# PGTN021_octasource_controls.net
KiCad netlist of a schematic drawn in EAGLE
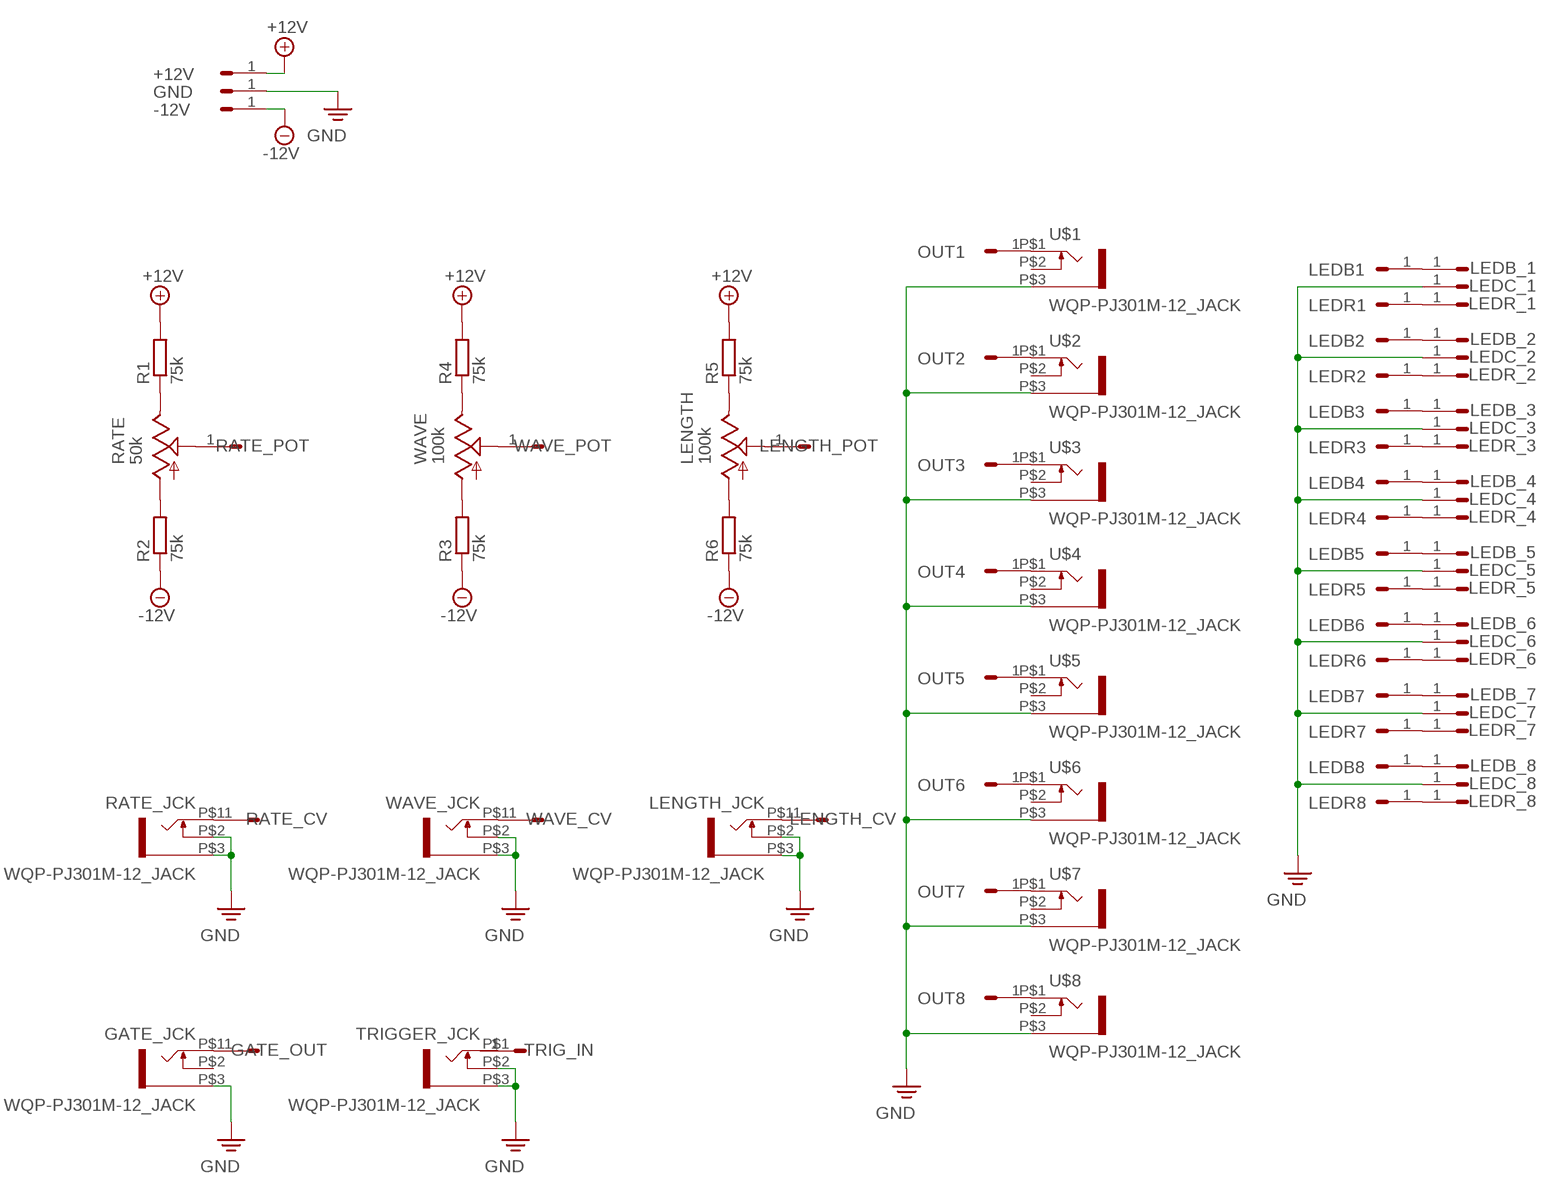
[diagram p0: schematic, sheet 1]

(export (version "E")
  (design (tool "Eeschema 10.0.6"))
  (components
    (comp (ref "+12V")
      (value "HEADER/MALE/01")
      (footprint "eagle-import:HEADER_MALE_01")
      (libsource (lib "eagle-import") (part "HEADER/MALE/01"))
    )
    (comp (ref "-12V")
      (value "HEADER/MALE/01")
      (footprint "eagle-import:HEADER_MALE_01")
      (libsource (lib "eagle-import") (part "HEADER/MALE/01"))
    )
    (comp (ref "GATE_JCK")
      (value "WQP-PJ301M-12_JACK")
      (footprint "eagle-import:WQP-PJ301M-12_JACK")
      (libsource (lib "eagle-import") (part "WQP-PJ301M-12_JACK"))
    )
    (comp (ref "GATE_OUT")
      (value "HEADER/MALE/01")
      (footprint "eagle-import:HEADER_MALE_01")
      (libsource (lib "eagle-import") (part "HEADER/MALE/01"))
    )
    (comp (ref "GND")
      (value "HEADER/MALE/01")
      (footprint "eagle-import:HEADER_MALE_01")
      (libsource (lib "eagle-import") (part "HEADER/MALE/01"))
    )
    (comp (ref "LEDB1")
      (value "HEADER/MALE/01")
      (footprint "eagle-import:HEADER_MALE_01")
      (libsource (lib "eagle-import") (part "HEADER/MALE/01"))
    )
    (comp (ref "LEDB2")
      (value "HEADER/MALE/01")
      (footprint "eagle-import:HEADER_MALE_01")
      (libsource (lib "eagle-import") (part "HEADER/MALE/01"))
    )
    (comp (ref "LEDB3")
      (value "HEADER/MALE/01")
      (footprint "eagle-import:HEADER_MALE_01")
      (libsource (lib "eagle-import") (part "HEADER/MALE/01"))
    )
    (comp (ref "LEDB4")
      (value "HEADER/MALE/01")
      (footprint "eagle-import:HEADER_MALE_01")
      (libsource (lib "eagle-import") (part "HEADER/MALE/01"))
    )
    (comp (ref "LEDB5")
      (value "HEADER/MALE/01")
      (footprint "eagle-import:HEADER_MALE_01")
      (libsource (lib "eagle-import") (part "HEADER/MALE/01"))
    )
    (comp (ref "LEDB6")
      (value "HEADER/MALE/01")
      (footprint "eagle-import:HEADER_MALE_01")
      (libsource (lib "eagle-import") (part "HEADER/MALE/01"))
    )
    (comp (ref "LEDB7")
      (value "HEADER/MALE/01")
      (footprint "eagle-import:HEADER_MALE_01")
      (libsource (lib "eagle-import") (part "HEADER/MALE/01"))
    )
    (comp (ref "LEDB8")
      (value "HEADER/MALE/01")
      (footprint "eagle-import:HEADER_MALE_01")
      (libsource (lib "eagle-import") (part "HEADER/MALE/01"))
    )
    (comp (ref "LEDB_1")
      (value "HEADER/MALE/01")
      (footprint "eagle-import:HEADER_MALE_01")
      (libsource (lib "eagle-import") (part "HEADER/MALE/01"))
    )
    (comp (ref "LEDB_2")
      (value "HEADER/MALE/01")
      (footprint "eagle-import:HEADER_MALE_01")
      (libsource (lib "eagle-import") (part "HEADER/MALE/01"))
    )
    (comp (ref "LEDB_3")
      (value "HEADER/MALE/01")
      (footprint "eagle-import:HEADER_MALE_01")
      (libsource (lib "eagle-import") (part "HEADER/MALE/01"))
    )
    (comp (ref "LEDB_4")
      (value "HEADER/MALE/01")
      (footprint "eagle-import:HEADER_MALE_01")
      (libsource (lib "eagle-import") (part "HEADER/MALE/01"))
    )
    (comp (ref "LEDB_5")
      (value "HEADER/MALE/01")
      (footprint "eagle-import:HEADER_MALE_01")
      (libsource (lib "eagle-import") (part "HEADER/MALE/01"))
    )
    (comp (ref "LEDB_6")
      (value "HEADER/MALE/01")
      (footprint "eagle-import:HEADER_MALE_01")
      (libsource (lib "eagle-import") (part "HEADER/MALE/01"))
    )
    (comp (ref "LEDB_7")
      (value "HEADER/MALE/01")
      (footprint "eagle-import:HEADER_MALE_01")
      (libsource (lib "eagle-import") (part "HEADER/MALE/01"))
    )
    (comp (ref "LEDB_8")
      (value "HEADER/MALE/01")
      (footprint "eagle-import:HEADER_MALE_01")
      (libsource (lib "eagle-import") (part "HEADER/MALE/01"))
    )
    (comp (ref "LEDC_1")
      (value "HEADER/MALE/01")
      (footprint "eagle-import:HEADER_MALE_01")
      (libsource (lib "eagle-import") (part "HEADER/MALE/01"))
    )
    (comp (ref "LEDC_2")
      (value "HEADER/MALE/01")
      (footprint "eagle-import:HEADER_MALE_01")
      (libsource (lib "eagle-import") (part "HEADER/MALE/01"))
    )
    (comp (ref "LEDC_3")
      (value "HEADER/MALE/01")
      (footprint "eagle-import:HEADER_MALE_01")
      (libsource (lib "eagle-import") (part "HEADER/MALE/01"))
    )
    (comp (ref "LEDC_4")
      (value "HEADER/MALE/01")
      (footprint "eagle-import:HEADER_MALE_01")
      (libsource (lib "eagle-import") (part "HEADER/MALE/01"))
    )
    (comp (ref "LEDC_5")
      (value "HEADER/MALE/01")
      (footprint "eagle-import:HEADER_MALE_01")
      (libsource (lib "eagle-import") (part "HEADER/MALE/01"))
    )
    (comp (ref "LEDC_6")
      (value "HEADER/MALE/01")
      (footprint "eagle-import:HEADER_MALE_01")
      (libsource (lib "eagle-import") (part "HEADER/MALE/01"))
    )
    (comp (ref "LEDC_7")
      (value "HEADER/MALE/01")
      (footprint "eagle-import:HEADER_MALE_01")
      (libsource (lib "eagle-import") (part "HEADER/MALE/01"))
    )
    (comp (ref "LEDC_8")
      (value "HEADER/MALE/01")
      (footprint "eagle-import:HEADER_MALE_01")
      (libsource (lib "eagle-import") (part "HEADER/MALE/01"))
    )
    (comp (ref "LEDR1")
      (value "HEADER/MALE/01")
      (footprint "eagle-import:HEADER_MALE_01")
      (libsource (lib "eagle-import") (part "HEADER/MALE/01"))
    )
    (comp (ref "LEDR2")
      (value "HEADER/MALE/01")
      (footprint "eagle-import:HEADER_MALE_01")
      (libsource (lib "eagle-import") (part "HEADER/MALE/01"))
    )
    (comp (ref "LEDR3")
      (value "HEADER/MALE/01")
      (footprint "eagle-import:HEADER_MALE_01")
      (libsource (lib "eagle-import") (part "HEADER/MALE/01"))
    )
    (comp (ref "LEDR4")
      (value "HEADER/MALE/01")
      (footprint "eagle-import:HEADER_MALE_01")
      (libsource (lib "eagle-import") (part "HEADER/MALE/01"))
    )
    (comp (ref "LEDR5")
      (value "HEADER/MALE/01")
      (footprint "eagle-import:HEADER_MALE_01")
      (libsource (lib "eagle-import") (part "HEADER/MALE/01"))
    )
    (comp (ref "LEDR6")
      (value "HEADER/MALE/01")
      (footprint "eagle-import:HEADER_MALE_01")
      (libsource (lib "eagle-import") (part "HEADER/MALE/01"))
    )
    (comp (ref "LEDR7")
      (value "HEADER/MALE/01")
      (footprint "eagle-import:HEADER_MALE_01")
      (libsource (lib "eagle-import") (part "HEADER/MALE/01"))
    )
    (comp (ref "LEDR8")
      (value "HEADER/MALE/01")
      (footprint "eagle-import:HEADER_MALE_01")
      (libsource (lib "eagle-import") (part "HEADER/MALE/01"))
    )
    (comp (ref "LEDR_1")
      (value "HEADER/MALE/01")
      (footprint "eagle-import:HEADER_MALE_01")
      (libsource (lib "eagle-import") (part "HEADER/MALE/01"))
    )
    (comp (ref "LEDR_2")
      (value "HEADER/MALE/01")
      (footprint "eagle-import:HEADER_MALE_01")
      (libsource (lib "eagle-import") (part "HEADER/MALE/01"))
    )
    (comp (ref "LEDR_3")
      (value "HEADER/MALE/01")
      (footprint "eagle-import:HEADER_MALE_01")
      (libsource (lib "eagle-import") (part "HEADER/MALE/01"))
    )
    (comp (ref "LEDR_4")
      (value "HEADER/MALE/01")
      (footprint "eagle-import:HEADER_MALE_01")
      (libsource (lib "eagle-import") (part "HEADER/MALE/01"))
    )
    (comp (ref "LEDR_5")
      (value "HEADER/MALE/01")
      (footprint "eagle-import:HEADER_MALE_01")
      (libsource (lib "eagle-import") (part "HEADER/MALE/01"))
    )
    (comp (ref "LEDR_6")
      (value "HEADER/MALE/01")
      (footprint "eagle-import:HEADER_MALE_01")
      (libsource (lib "eagle-import") (part "HEADER/MALE/01"))
    )
    (comp (ref "LEDR_7")
      (value "HEADER/MALE/01")
      (footprint "eagle-import:HEADER_MALE_01")
      (libsource (lib "eagle-import") (part "HEADER/MALE/01"))
    )
    (comp (ref "LEDR_8")
      (value "HEADER/MALE/01")
      (footprint "eagle-import:HEADER_MALE_01")
      (libsource (lib "eagle-import") (part "HEADER/MALE/01"))
    )
    (comp (ref "LENGTH")
      (value "100k")
      (footprint "eagle-import:9MM_SNAP-IN_POT")
      (libsource (lib "eagle-import") (part "9MM_SNAP-IN_POT_"))
    )
    (comp (ref "LENGTH_CV")
      (value "HEADER/MALE/01")
      (footprint "eagle-import:HEADER_MALE_01")
      (libsource (lib "eagle-import") (part "HEADER/MALE/01"))
    )
    (comp (ref "LENGTH_JCK")
      (value "WQP-PJ301M-12_JACK")
      (footprint "eagle-import:WQP-PJ301M-12_JACK")
      (libsource (lib "eagle-import") (part "WQP-PJ301M-12_JACK"))
    )
    (comp (ref "LENGTH_POT")
      (value "HEADER/MALE/01")
      (footprint "eagle-import:HEADER_MALE_01")
      (libsource (lib "eagle-import") (part "HEADER/MALE/01"))
    )
    (comp (ref "OUT1")
      (value "HEADER/MALE/01")
      (footprint "eagle-import:HEADER_MALE_01")
      (libsource (lib "eagle-import") (part "HEADER/MALE/01"))
    )
    (comp (ref "OUT2")
      (value "HEADER/MALE/01")
      (footprint "eagle-import:HEADER_MALE_01")
      (libsource (lib "eagle-import") (part "HEADER/MALE/01"))
    )
    (comp (ref "OUT3")
      (value "HEADER/MALE/01")
      (footprint "eagle-import:HEADER_MALE_01")
      (libsource (lib "eagle-import") (part "HEADER/MALE/01"))
    )
    (comp (ref "OUT4")
      (value "HEADER/MALE/01")
      (footprint "eagle-import:HEADER_MALE_01")
      (libsource (lib "eagle-import") (part "HEADER/MALE/01"))
    )
    (comp (ref "OUT5")
      (value "HEADER/MALE/01")
      (footprint "eagle-import:HEADER_MALE_01")
      (libsource (lib "eagle-import") (part "HEADER/MALE/01"))
    )
    (comp (ref "OUT6")
      (value "HEADER/MALE/01")
      (footprint "eagle-import:HEADER_MALE_01")
      (libsource (lib "eagle-import") (part "HEADER/MALE/01"))
    )
    (comp (ref "OUT7")
      (value "HEADER/MALE/01")
      (footprint "eagle-import:HEADER_MALE_01")
      (libsource (lib "eagle-import") (part "HEADER/MALE/01"))
    )
    (comp (ref "OUT8")
      (value "HEADER/MALE/01")
      (footprint "eagle-import:HEADER_MALE_01")
      (libsource (lib "eagle-import") (part "HEADER/MALE/01"))
    )
    (comp (ref "R1")
      (value "75k")
      (footprint "eagle-import:RESISTOR_7.5")
      (libsource (lib "eagle-import") (part "RESISTORRESISTOR/UPRIGHT/7.5"))
    )
    (comp (ref "R2")
      (value "75k")
      (footprint "eagle-import:RESISTOR_7.5")
      (libsource (lib "eagle-import") (part "RESISTORRESISTOR/UPRIGHT/7.5"))
    )
    (comp (ref "R3")
      (value "75k")
      (footprint "eagle-import:RESISTOR_7.5")
      (libsource (lib "eagle-import") (part "RESISTORRESISTOR/UPRIGHT/7.5"))
    )
    (comp (ref "R4")
      (value "75k")
      (footprint "eagle-import:RESISTOR_7.5")
      (libsource (lib "eagle-import") (part "RESISTORRESISTOR/UPRIGHT/7.5"))
    )
    (comp (ref "R5")
      (value "75k")
      (footprint "eagle-import:RESISTOR_7.5")
      (libsource (lib "eagle-import") (part "RESISTORRESISTOR/UPRIGHT/7.5"))
    )
    (comp (ref "R6")
      (value "75k")
      (footprint "eagle-import:RESISTOR_7.5")
      (libsource (lib "eagle-import") (part "RESISTORRESISTOR/UPRIGHT/7.5"))
    )
    (comp (ref "RATE")
      (value "50k")
      (footprint "eagle-import:9MM_SNAP-IN_POT")
      (libsource (lib "eagle-import") (part "9MM_SNAP-IN_POT_"))
    )
    (comp (ref "RATE_CV")
      (value "HEADER/MALE/01")
      (footprint "eagle-import:HEADER_MALE_01")
      (libsource (lib "eagle-import") (part "HEADER/MALE/01"))
    )
    (comp (ref "RATE_JCK")
      (value "WQP-PJ301M-12_JACK")
      (footprint "eagle-import:WQP-PJ301M-12_JACK")
      (libsource (lib "eagle-import") (part "WQP-PJ301M-12_JACK"))
    )
    (comp (ref "RATE_POT")
      (value "HEADER/MALE/01")
      (footprint "eagle-import:HEADER_MALE_01")
      (libsource (lib "eagle-import") (part "HEADER/MALE/01"))
    )
    (comp (ref "TRIGGER_JCK")
      (value "WQP-PJ301M-12_JACK")
      (footprint "eagle-import:WQP-PJ301M-12_JACK")
      (libsource (lib "eagle-import") (part "WQP-PJ301M-12_JACK"))
    )
    (comp (ref "TRIG_IN")
      (value "HEADER/MALE/01")
      (footprint "eagle-import:HEADER_MALE_01")
      (libsource (lib "eagle-import") (part "HEADER/MALE/01"))
    )
    (comp (ref "U$1")
      (value "WQP-PJ301M-12_JACK")
      (footprint "eagle-import:WQP-PJ301M-12_JACK")
      (libsource (lib "eagle-import") (part "WQP-PJ301M-12_JACK"))
    )
    (comp (ref "U$2")
      (value "WQP-PJ301M-12_JACK")
      (footprint "eagle-import:WQP-PJ301M-12_JACK")
      (libsource (lib "eagle-import") (part "WQP-PJ301M-12_JACK"))
    )
    (comp (ref "U$3")
      (value "WQP-PJ301M-12_JACK")
      (footprint "eagle-import:WQP-PJ301M-12_JACK")
      (libsource (lib "eagle-import") (part "WQP-PJ301M-12_JACK"))
    )
    (comp (ref "U$4")
      (value "WQP-PJ301M-12_JACK")
      (footprint "eagle-import:WQP-PJ301M-12_JACK")
      (libsource (lib "eagle-import") (part "WQP-PJ301M-12_JACK"))
    )
    (comp (ref "U$5")
      (value "WQP-PJ301M-12_JACK")
      (footprint "eagle-import:WQP-PJ301M-12_JACK")
      (libsource (lib "eagle-import") (part "WQP-PJ301M-12_JACK"))
    )
    (comp (ref "U$6")
      (value "WQP-PJ301M-12_JACK")
      (footprint "eagle-import:WQP-PJ301M-12_JACK")
      (libsource (lib "eagle-import") (part "WQP-PJ301M-12_JACK"))
    )
    (comp (ref "U$7")
      (value "WQP-PJ301M-12_JACK")
      (footprint "eagle-import:WQP-PJ301M-12_JACK")
      (libsource (lib "eagle-import") (part "WQP-PJ301M-12_JACK"))
    )
    (comp (ref "U$8")
      (value "WQP-PJ301M-12_JACK")
      (footprint "eagle-import:WQP-PJ301M-12_JACK")
      (libsource (lib "eagle-import") (part "WQP-PJ301M-12_JACK"))
    )
    (comp (ref "WAVE")
      (value "100k")
      (footprint "eagle-import:9MM_SNAP-IN_POT")
      (libsource (lib "eagle-import") (part "9MM_SNAP-IN_POT_"))
    )
    (comp (ref "WAVE_CV")
      (value "HEADER/MALE/01")
      (footprint "eagle-import:HEADER_MALE_01")
      (libsource (lib "eagle-import") (part "HEADER/MALE/01"))
    )
    (comp (ref "WAVE_JCK")
      (value "WQP-PJ301M-12_JACK")
      (footprint "eagle-import:WQP-PJ301M-12_JACK")
      (libsource (lib "eagle-import") (part "WQP-PJ301M-12_JACK"))
    )
    (comp (ref "WAVE_POT")
      (value "HEADER/MALE/01")
      (footprint "eagle-import:HEADER_MALE_01")
      (libsource (lib "eagle-import") (part "HEADER/MALE/01"))
    )
  )
  (nets
    (net (code "1") (name "+12V") (class "Default")
      (node (ref "+12V") (pin "1") (pinfunction "3_1") (pintype "passive"))
      (node (ref "R1") (pin "2") (pinfunction "2_2") (pintype "passive"))
      (node (ref "R4") (pin "2") (pinfunction "2_2") (pintype "passive"))
      (node (ref "R5") (pin "2") (pinfunction "2_2") (pintype "passive"))
    )
    (net (code "2") (name "-12V") (class "Default")
      (node (ref "-12V") (pin "1") (pinfunction "3_1") (pintype "passive"))
      (node (ref "R2") (pin "1") (pinfunction "1_1") (pintype "passive"))
      (node (ref "R3") (pin "1") (pinfunction "1_1") (pintype "passive"))
      (node (ref "R6") (pin "1") (pinfunction "1_1") (pintype "passive"))
    )
    (net (code "3") (name "GND") (class "Default")
      (node (ref "GATE_JCK") (pin "P$3") (pinfunction "1_P$3") (pintype "passive"))
      (node (ref "GND") (pin "1") (pinfunction "3_1") (pintype "passive"))
      (node (ref "LEDC_1") (pin "1") (pinfunction "3_1") (pintype "passive"))
      (node (ref "LEDC_2") (pin "1") (pinfunction "3_1") (pintype "passive"))
      (node (ref "LEDC_3") (pin "1") (pinfunction "3_1") (pintype "passive"))
      (node (ref "LEDC_4") (pin "1") (pinfunction "3_1") (pintype "passive"))
      (node (ref "LEDC_5") (pin "1") (pinfunction "3_1") (pintype "passive"))
      (node (ref "LEDC_6") (pin "1") (pinfunction "3_1") (pintype "passive"))
      (node (ref "LEDC_7") (pin "1") (pinfunction "3_1") (pintype "passive"))
      (node (ref "LEDC_8") (pin "1") (pinfunction "3_1") (pintype "passive"))
      (node (ref "LENGTH_JCK") (pin "P$2") (pinfunction "3_P$2") (pintype "passive"))
      (node (ref "LENGTH_JCK") (pin "P$3") (pinfunction "1_P$3") (pintype "passive"))
      (node (ref "RATE_JCK") (pin "P$2") (pinfunction "3_P$2") (pintype "passive"))
      (node (ref "RATE_JCK") (pin "P$3") (pinfunction "1_P$3") (pintype "passive"))
      (node (ref "TRIGGER_JCK") (pin "P$2") (pinfunction "3_P$2") (pintype "passive"))
      (node (ref "TRIGGER_JCK") (pin "P$3") (pinfunction "1_P$3") (pintype "passive"))
      (node (ref "U$1") (pin "P$3") (pinfunction "1_P$3") (pintype "passive"))
      (node (ref "U$2") (pin "P$3") (pinfunction "1_P$3") (pintype "passive"))
      (node (ref "U$3") (pin "P$3") (pinfunction "1_P$3") (pintype "passive"))
      (node (ref "U$4") (pin "P$3") (pinfunction "1_P$3") (pintype "passive"))
      (node (ref "U$5") (pin "P$3") (pinfunction "1_P$3") (pintype "passive"))
      (node (ref "U$6") (pin "P$3") (pinfunction "1_P$3") (pintype "passive"))
      (node (ref "U$7") (pin "P$3") (pinfunction "1_P$3") (pintype "passive"))
      (node (ref "U$8") (pin "P$3") (pinfunction "1_P$3") (pintype "passive"))
      (node (ref "WAVE_JCK") (pin "P$2") (pinfunction "3_P$2") (pintype "passive"))
      (node (ref "WAVE_JCK") (pin "P$3") (pinfunction "1_P$3") (pintype "passive"))
    )
    (net (code "4") (name "Net-(GATE_JCK-2)") (class "Default")
      (node (ref "GATE_JCK") (pin "P$1") (pinfunction "2_P$1") (pintype "passive"))
      (node (ref "GATE_OUT") (pin "1") (pinfunction "3_1") (pintype "passive"))
    )
    (net (code "5") (name "Net-(LEDB1-3)") (class "Default")
      (node (ref "LEDB1") (pin "1") (pinfunction "3_1") (pintype "passive"))
      (node (ref "LEDB_1") (pin "1") (pinfunction "3_1") (pintype "passive"))
    )
    (net (code "6") (name "Net-(LEDB2-3)") (class "Default")
      (node (ref "LEDB2") (pin "1") (pinfunction "3_1") (pintype "passive"))
      (node (ref "LEDB_2") (pin "1") (pinfunction "3_1") (pintype "passive"))
    )
    (net (code "7") (name "Net-(LEDB3-3)") (class "Default")
      (node (ref "LEDB3") (pin "1") (pinfunction "3_1") (pintype "passive"))
      (node (ref "LEDB_3") (pin "1") (pinfunction "3_1") (pintype "passive"))
    )
    (net (code "8") (name "Net-(LEDB4-3)") (class "Default")
      (node (ref "LEDB4") (pin "1") (pinfunction "3_1") (pintype "passive"))
      (node (ref "LEDB_4") (pin "1") (pinfunction "3_1") (pintype "passive"))
    )
    (net (code "9") (name "Net-(LEDB5-3)") (class "Default")
      (node (ref "LEDB5") (pin "1") (pinfunction "3_1") (pintype "passive"))
      (node (ref "LEDB_5") (pin "1") (pinfunction "3_1") (pintype "passive"))
    )
    (net (code "10") (name "Net-(LEDB6-3)") (class "Default")
      (node (ref "LEDB6") (pin "1") (pinfunction "3_1") (pintype "passive"))
      (node (ref "LEDB_6") (pin "1") (pinfunction "3_1") (pintype "passive"))
    )
    (net (code "11") (name "Net-(LEDB7-3)") (class "Default")
      (node (ref "LEDB7") (pin "1") (pinfunction "3_1") (pintype "passive"))
      (node (ref "LEDB_7") (pin "1") (pinfunction "3_1") (pintype "passive"))
    )
    (net (code "12") (name "Net-(LEDB8-3)") (class "Default")
      (node (ref "LEDB8") (pin "1") (pinfunction "3_1") (pintype "passive"))
      (node (ref "LEDB_8") (pin "1") (pinfunction "3_1") (pintype "passive"))
    )
    (net (code "13") (name "Net-(LEDR1-3)") (class "Default")
      (node (ref "LEDR1") (pin "1") (pinfunction "3_1") (pintype "passive"))
      (node (ref "LEDR_1") (pin "1") (pinfunction "3_1") (pintype "passive"))
    )
    (net (code "14") (name "Net-(LEDR2-3)") (class "Default")
      (node (ref "LEDR2") (pin "1") (pinfunction "3_1") (pintype "passive"))
      (node (ref "LEDR_2") (pin "1") (pinfunction "3_1") (pintype "passive"))
    )
    (net (code "15") (name "Net-(LEDR3-3)") (class "Default")
      (node (ref "LEDR3") (pin "1") (pinfunction "3_1") (pintype "passive"))
      (node (ref "LEDR_3") (pin "1") (pinfunction "3_1") (pintype "passive"))
    )
    (net (code "16") (name "Net-(LEDR4-3)") (class "Default")
      (node (ref "LEDR4") (pin "1") (pinfunction "3_1") (pintype "passive"))
      (node (ref "LEDR_4") (pin "1") (pinfunction "3_1") (pintype "passive"))
    )
    (net (code "17") (name "Net-(LEDR5-3)") (class "Default")
      (node (ref "LEDR5") (pin "1") (pinfunction "3_1") (pintype "passive"))
      (node (ref "LEDR_5") (pin "1") (pinfunction "3_1") (pintype "passive"))
    )
    (net (code "18") (name "Net-(LEDR6-3)") (class "Default")
      (node (ref "LEDR6") (pin "1") (pinfunction "3_1") (pintype "passive"))
      (node (ref "LEDR_6") (pin "1") (pinfunction "3_1") (pintype "passive"))
    )
    (net (code "19") (name "Net-(LEDR7-3)") (class "Default")
      (node (ref "LEDR7") (pin "1") (pinfunction "3_1") (pintype "passive"))
      (node (ref "LEDR_7") (pin "1") (pinfunction "3_1") (pintype "passive"))
    )
    (net (code "20") (name "Net-(LEDR8-3)") (class "Default")
      (node (ref "LEDR8") (pin "1") (pinfunction "3_1") (pintype "passive"))
      (node (ref "LEDR_8") (pin "1") (pinfunction "3_1") (pintype "passive"))
    )
    (net (code "21") (name "Net-(LENGTH-A)") (class "Default")
      (node (ref "LENGTH") (pin "1") (pinfunction "A_1") (pintype "passive"))
      (node (ref "R6") (pin "2") (pinfunction "2_2") (pintype "passive"))
    )
    (net (code "22") (name "Net-(LENGTH-E)") (class "Default")
      (node (ref "LENGTH") (pin "3") (pinfunction "E_3") (pintype "passive"))
      (node (ref "R5") (pin "1") (pinfunction "1_1") (pintype "passive"))
    )
    (net (code "23") (name "Net-(LENGTH-S)") (class "Default")
      (node (ref "LENGTH") (pin "2") (pinfunction "S_2") (pintype "passive"))
      (node (ref "LENGTH_POT") (pin "1") (pinfunction "3_1") (pintype "passive"))
    )
    (net (code "24") (name "Net-(LENGTH_CV-3)") (class "Default")
      (node (ref "LENGTH_CV") (pin "1") (pinfunction "3_1") (pintype "passive"))
      (node (ref "LENGTH_JCK") (pin "P$1") (pinfunction "2_P$1") (pintype "passive"))
    )
    (net (code "25") (name "Net-(OUT1-3)") (class "Default")
      (node (ref "OUT1") (pin "1") (pinfunction "3_1") (pintype "passive"))
      (node (ref "U$1") (pin "P$1") (pinfunction "2_P$1") (pintype "passive"))
    )
    (net (code "26") (name "Net-(OUT2-3)") (class "Default")
      (node (ref "OUT2") (pin "1") (pinfunction "3_1") (pintype "passive"))
      (node (ref "U$2") (pin "P$1") (pinfunction "2_P$1") (pintype "passive"))
    )
    (net (code "27") (name "Net-(OUT3-3)") (class "Default")
      (node (ref "OUT3") (pin "1") (pinfunction "3_1") (pintype "passive"))
      (node (ref "U$3") (pin "P$1") (pinfunction "2_P$1") (pintype "passive"))
    )
    (net (code "28") (name "Net-(OUT4-3)") (class "Default")
      (node (ref "OUT4") (pin "1") (pinfunction "3_1") (pintype "passive"))
      (node (ref "U$4") (pin "P$1") (pinfunction "2_P$1") (pintype "passive"))
    )
    (net (code "29") (name "Net-(OUT5-3)") (class "Default")
      (node (ref "OUT5") (pin "1") (pinfunction "3_1") (pintype "passive"))
      (node (ref "U$5") (pin "P$1") (pinfunction "2_P$1") (pintype "passive"))
    )
    (net (code "30") (name "Net-(OUT6-3)") (class "Default")
      (node (ref "OUT6") (pin "1") (pinfunction "3_1") (pintype "passive"))
      (node (ref "U$6") (pin "P$1") (pinfunction "2_P$1") (pintype "passive"))
    )
    (net (code "31") (name "Net-(OUT7-3)") (class "Default")
      (node (ref "OUT7") (pin "1") (pinfunction "3_1") (pintype "passive"))
      (node (ref "U$7") (pin "P$1") (pinfunction "2_P$1") (pintype "passive"))
    )
    (net (code "32") (name "Net-(OUT8-3)") (class "Default")
      (node (ref "OUT8") (pin "1") (pinfunction "3_1") (pintype "passive"))
      (node (ref "U$8") (pin "P$1") (pinfunction "2_P$1") (pintype "passive"))
    )
    (net (code "33") (name "Net-(RATE-A)") (class "Default")
      (node (ref "R2") (pin "2") (pinfunction "2_2") (pintype "passive"))
      (node (ref "RATE") (pin "1") (pinfunction "A_1") (pintype "passive"))
    )
    (net (code "34") (name "Net-(RATE-E)") (class "Default")
      (node (ref "R1") (pin "1") (pinfunction "1_1") (pintype "passive"))
      (node (ref "RATE") (pin "3") (pinfunction "E_3") (pintype "passive"))
    )
    (net (code "35") (name "Net-(RATE-S)") (class "Default")
      (node (ref "RATE") (pin "2") (pinfunction "S_2") (pintype "passive"))
      (node (ref "RATE_POT") (pin "1") (pinfunction "3_1") (pintype "passive"))
    )
    (net (code "36") (name "Net-(RATE_CV-3)") (class "Default")
      (node (ref "RATE_CV") (pin "1") (pinfunction "3_1") (pintype "passive"))
      (node (ref "RATE_JCK") (pin "P$1") (pinfunction "2_P$1") (pintype "passive"))
    )
    (net (code "37") (name "Net-(WAVE-A)") (class "Default")
      (node (ref "R3") (pin "2") (pinfunction "2_2") (pintype "passive"))
      (node (ref "WAVE") (pin "1") (pinfunction "A_1") (pintype "passive"))
    )
    (net (code "38") (name "Net-(WAVE-E)") (class "Default")
      (node (ref "R4") (pin "1") (pinfunction "1_1") (pintype "passive"))
      (node (ref "WAVE") (pin "3") (pinfunction "E_3") (pintype "passive"))
    )
    (net (code "39") (name "Net-(WAVE-S)") (class "Default")
      (node (ref "WAVE") (pin "2") (pinfunction "S_2") (pintype "passive"))
      (node (ref "WAVE_POT") (pin "1") (pinfunction "3_1") (pintype "passive"))
    )
    (net (code "40") (name "Net-(WAVE_CV-3)") (class "Default")
      (node (ref "WAVE_CV") (pin "1") (pinfunction "3_1") (pintype "passive"))
      (node (ref "WAVE_JCK") (pin "P$1") (pinfunction "2_P$1") (pintype "passive"))
    )
    (net (code "41") (name "unconnected-(GATE_JCK-3-PadP$2)") (class "Default")
      (node (ref "GATE_JCK") (pin "P$2") (pinfunction "3_P$2") (pintype "passive"))
    )
    (net (code "42") (name "unconnected-(TRIGGER_JCK-2-PadP$1)") (class "Default")
      (node (ref "TRIGGER_JCK") (pin "P$1") (pinfunction "2_P$1") (pintype "passive"))
    )
    (net (code "43") (name "unconnected-(TRIG_IN-3-Pad1)") (class "Default")
      (node (ref "TRIG_IN") (pin "1") (pinfunction "3_1") (pintype "passive"))
    )
    (net (code "44") (name "unconnected-(U$1-3-PadP$2)") (class "Default")
      (node (ref "U$1") (pin "P$2") (pinfunction "3_P$2") (pintype "passive"))
    )
    (net (code "45") (name "unconnected-(U$2-3-PadP$2)") (class "Default")
      (node (ref "U$2") (pin "P$2") (pinfunction "3_P$2") (pintype "passive"))
    )
    (net (code "46") (name "unconnected-(U$3-3-PadP$2)") (class "Default")
      (node (ref "U$3") (pin "P$2") (pinfunction "3_P$2") (pintype "passive"))
    )
    (net (code "47") (name "unconnected-(U$4-3-PadP$2)") (class "Default")
      (node (ref "U$4") (pin "P$2") (pinfunction "3_P$2") (pintype "passive"))
    )
    (net (code "48") (name "unconnected-(U$5-3-PadP$2)") (class "Default")
      (node (ref "U$5") (pin "P$2") (pinfunction "3_P$2") (pintype "passive"))
    )
    (net (code "49") (name "unconnected-(U$6-3-PadP$2)") (class "Default")
      (node (ref "U$6") (pin "P$2") (pinfunction "3_P$2") (pintype "passive"))
    )
    (net (code "50") (name "unconnected-(U$7-3-PadP$2)") (class "Default")
      (node (ref "U$7") (pin "P$2") (pinfunction "3_P$2") (pintype "passive"))
    )
    (net (code "51") (name "unconnected-(U$8-3-PadP$2)") (class "Default")
      (node (ref "U$8") (pin "P$2") (pinfunction "3_P$2") (pintype "passive"))
    )
  )
)
